# Ethernet.net
KiCad netlist of a schematic drawn in Altium Designer
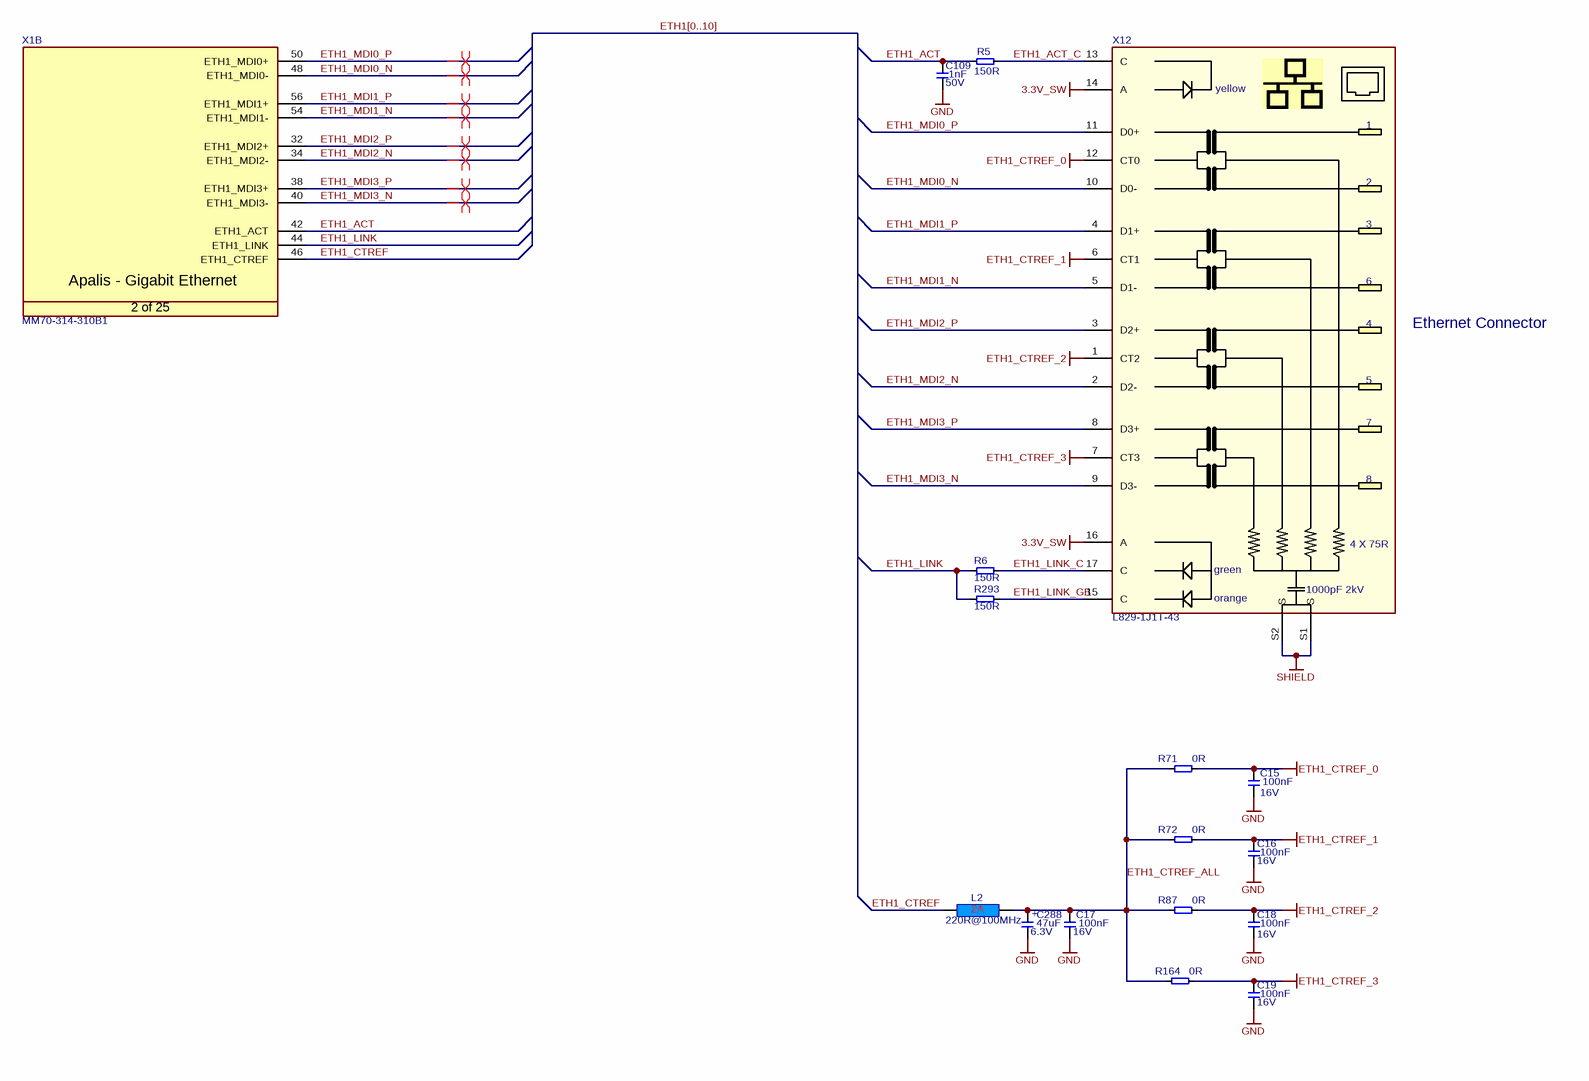
[diagram p0: Ethernet.SchDoc]

(export (version "E")
  (design (tool "Eeschema 10.0.6"))
  (components
    (comp (ref "C15")
      (value "100nF")
      (footprint "T_CAPC0603X33N")
      (description "Capacitor Ceramic X7R 100nF 16V 10% 0603")
      (fields (field (name "TOLERANCE") "10%") (field (name "RATING") "16V"))
      (libsource (lib "Apalis Evaluation Board") (part "C-X7R-100nF-16V-10%-0603"))
    )
    (comp (ref "C16")
      (value "100nF")
      (footprint "T_CAPC0603X33N")
      (description "Capacitor Ceramic X7R 100nF 16V 10% 0603")
      (fields (field (name "TOLERANCE") "10%") (field (name "RATING") "16V"))
      (libsource (lib "Apalis Evaluation Board") (part "C-X7R-100nF-16V-10%-0603"))
    )
    (comp (ref "C17")
      (value "100nF")
      (footprint "T_CAPC0603X33N")
      (description "Capacitor Ceramic X7R 100nF 16V 10% 0603")
      (fields (field (name "TOLERANCE") "10%") (field (name "RATING") "16V"))
      (libsource (lib "Apalis Evaluation Board") (part "C-X7R-100nF-16V-10%-0603"))
    )
    (comp (ref "C18")
      (value "100nF")
      (footprint "T_CAPC0603X33N")
      (description "Capacitor Ceramic X7R 100nF 16V 10% 0603")
      (fields (field (name "TOLERANCE") "10%") (field (name "RATING") "16V"))
      (libsource (lib "Apalis Evaluation Board") (part "C-X7R-100nF-16V-10%-0603"))
    )
    (comp (ref "C19")
      (value "100nF")
      (footprint "T_CAPC0603X33N")
      (description "Capacitor Ceramic X7R 100nF 16V 10% 0603")
      (fields (field (name "TOLERANCE") "10%") (field (name "RATING") "16V"))
      (libsource (lib "Apalis Evaluation Board") (part "C-X7R-100nF-16V-10%-0603"))
    )
    (comp (ref "C109")
      (value "1nF")
      (footprint "CAPC1005X60N")
      (description "Capacitor Ceramic X7R 1nF 50V 10% 0402")
      (fields (field (name "TOLERANCE") "10%") (field (name "RATING") "50V"))
      (libsource (lib "Apalis Evaluation Board") (part "C-X7R-1nF-50V-10%-0402"))
    )
    (comp (ref "C288")
      (value "47uF")
      (footprint "T_CAPMP3216X180N")
      (description "Capacitor TA 47uF 6.3V 20% 3216")
      (fields (field (name "TOLERANCE") "20%") (field (name "RATING") "6.3V"))
      (libsource (lib "Apalis Evaluation Board") (part "C-TA-47uF-6.3V-20%-3216"))
    )
    (comp (ref "L2")
      (value "220R@100MHz")
      (footprint "INDC1608X95N")
      (description "220R@100MHz 2A EMI FILTER")
      (fields (field (name "TOLERANCE") "25%"))
      (libsource (lib "Apalis Evaluation Board") (part "L-220R@100MHz-2A-25%-0603"))
    )
    (comp (ref "R5")
      (value "150R")
      (footprint "t_RESC0603X30N")
      (description "Resistor 150 ohm 63mW 1% 0603")
      (fields (field (name "TOLERANCE") "1%"))
      (libsource (lib "Apalis Evaluation Board") (part "R-150R-63mW-1%-0603"))
    )
    (comp (ref "R6")
      (value "150R")
      (footprint "t_RESC0603X30N")
      (description "Resistor 150 ohm 63mW 1% 0603")
      (fields (field (name "TOLERANCE") "1%"))
      (libsource (lib "Apalis Evaluation Board") (part "R-150R-63mW-1%-0603"))
    )
    (comp (ref "R71")
      (value "0R")
      (footprint "T_RESC0603X30N")
      (description "Resistor 0 ohm 63mW 1% 0603")
      (fields (field (name "TOLERANCE") "1%"))
      (libsource (lib "Apalis Evaluation Board") (part "R-0R-63mW-1%-0603"))
    )
    (comp (ref "R72")
      (value "0R")
      (footprint "T_RESC0603X30N")
      (description "Resistor 0 ohm 63mW 1% 0603")
      (fields (field (name "TOLERANCE") "1%"))
      (libsource (lib "Apalis Evaluation Board") (part "R-0R-63mW-1%-0603"))
    )
    (comp (ref "R87")
      (value "0R")
      (footprint "T_RESC0603X30N")
      (description "Resistor 0 ohm 63mW 1% 0603")
      (fields (field (name "TOLERANCE") "1%"))
      (libsource (lib "Apalis Evaluation Board") (part "R-0R-63mW-1%-0603"))
    )
    (comp (ref "R164")
      (value "0R")
      (footprint "T_RESC0603X30N")
      (description "Resistor 0 ohm 63mW 1% 0603")
      (fields (field (name "TOLERANCE") "1%"))
      (libsource (lib "Apalis Evaluation Board") (part "R-0R-63mW-1%-0603"))
    )
    (comp (ref "R293")
      (value "150R")
      (footprint "t_RESC0603X30N")
      (description "Resistor 150 ohm 63mW 1% 0603")
      (fields (field (name "TOLERANCE") "1%"))
      (libsource (lib "Apalis Evaluation Board") (part "R-150R-63mW-1%-0603"))
    )
    (comp (ref "X1")
      (value "CON-JAE-MM70-314-310B1-314-0.5mm")
      (footprint "T_JAE_MM70-314-310B1")
      (description "MXM3 Connector")
      (fields (field (name "MANUFACTURER PART NO.") "MM70-314-310B1"))
      (libsource (lib "Apalis Evaluation Board") (part "CON-JAE-MM70-314-310B1-314-0.5mm"))
    )
    (comp (ref "X12")
      (value "L829-1J1T-43")
      (footprint "T_BEL_L829-1J1T-43")
      (description "Low profile 10/100/1G Mag Jack")
      (fields (field (name "MANUFACTURER PART NO.") "L829-1J1T-43"))
      (libsource (lib "Apalis Evaluation Board") (part "CON-BEL-L829-1J1T-43"))
    )
  )
  (nets
    (net (code "13") (name "/ETH1_ACT") (class "Default")
      (node (ref "C109") (pin "2") (pinfunction "2_2") (pintype "passive"))
      (node (ref "R5") (pin "1") (pinfunction "1_1") (pintype "passive"))
      (node (ref "X1") (pin "42") (pinfunction "ETH1_ACT_42") (pintype "passive"))
    )
    (net (code "14") (name "/ETH1_ACT_C") (class "Default")
      (node (ref "R5") (pin "2") (pinfunction "2_2") (pintype "passive"))
      (node (ref "X12") (pin "13") (pinfunction "C_13") (pintype "passive"))
    )
    (net (code "15") (name "/ETH1_CTREF") (class "Default")
      (node (ref "L2") (pin "1") (pinfunction "1_1") (pintype "passive"))
      (node (ref "X1") (pin "46") (pinfunction "ETH1_CTREF_46") (pintype "passive"))
    )
    (net (code "16") (name "/ETH1_CTREF_ALL") (class "Default")
      (node (ref "C17") (pin "2") (pinfunction "2_2") (pintype "passive"))
      (node (ref "C288") (pin "1") (pinfunction "1_1") (pintype "passive"))
      (node (ref "L2") (pin "2") (pinfunction "2_2") (pintype "passive"))
      (node (ref "R164") (pin "1") (pinfunction "1_1") (pintype "passive"))
      (node (ref "R71") (pin "1") (pinfunction "1_1") (pintype "passive"))
      (node (ref "R72") (pin "1") (pinfunction "1_1") (pintype "passive"))
      (node (ref "R87") (pin "1") (pinfunction "1_1") (pintype "passive"))
    )
    (net (code "17") (name "/ETH1_LINK") (class "Default")
      (node (ref "R293") (pin "1") (pinfunction "1_1") (pintype "passive"))
      (node (ref "R6") (pin "1") (pinfunction "1_1") (pintype "passive"))
      (node (ref "X1") (pin "44") (pinfunction "ETH1_LINK_44") (pintype "passive"))
    )
    (net (code "18") (name "/ETH1_LINK_C") (class "Default")
      (node (ref "R6") (pin "2") (pinfunction "2_2") (pintype "passive"))
      (node (ref "X12") (pin "17") (pinfunction "C_17") (pintype "passive"))
    )
    (net (code "19") (name "/ETH1_LINK_GB") (class "Default")
      (node (ref "R293") (pin "2") (pinfunction "2_2") (pintype "passive"))
      (node (ref "X12") (pin "15") (pinfunction "C_15") (pintype "passive"))
    )
    (net (code "20") (name "/ETH1_MDI0_N") (class "Default")
      (node (ref "X1") (pin "48") (pinfunction "ETH1_MDI0-_48") (pintype "passive"))
      (node (ref "X12") (pin "10") (pinfunction "D0-_10") (pintype "passive"))
    )
    (net (code "21") (name "/ETH1_MDI0_P") (class "Default")
      (node (ref "X1") (pin "50") (pinfunction "ETH1_MDI0+_50") (pintype "passive"))
      (node (ref "X12") (pin "11") (pinfunction "D0+_11") (pintype "passive"))
    )
    (net (code "22") (name "/ETH1_MDI1_N") (class "Default")
      (node (ref "X1") (pin "54") (pinfunction "ETH1_MDI1-_54") (pintype "passive"))
      (node (ref "X12") (pin "5") (pinfunction "D1-_5") (pintype "passive"))
    )
    (net (code "23") (name "/ETH1_MDI1_P") (class "Default")
      (node (ref "X1") (pin "56") (pinfunction "ETH1_MDI1+_56") (pintype "passive"))
      (node (ref "X12") (pin "4") (pinfunction "D1+_4") (pintype "passive"))
    )
    (net (code "24") (name "/ETH1_MDI2_N") (class "Default")
      (node (ref "X1") (pin "34") (pinfunction "ETH1_MDI2-_34") (pintype "passive"))
      (node (ref "X12") (pin "2") (pinfunction "D2-_2") (pintype "passive"))
    )
    (net (code "25") (name "/ETH1_MDI2_P") (class "Default")
      (node (ref "X1") (pin "32") (pinfunction "ETH1_MDI2+_32") (pintype "passive"))
      (node (ref "X12") (pin "3") (pinfunction "D2+_3") (pintype "passive"))
    )
    (net (code "26") (name "/ETH1_MDI3_N") (class "Default")
      (node (ref "X1") (pin "40") (pinfunction "ETH1_MDI3-_40") (pintype "passive"))
      (node (ref "X12") (pin "9") (pinfunction "D3-_9") (pintype "passive"))
    )
    (net (code "27") (name "/ETH1_MDI3_P") (class "Default")
      (node (ref "X1") (pin "38") (pinfunction "ETH1_MDI3+_38") (pintype "passive"))
      (node (ref "X12") (pin "8") (pinfunction "D3+_8") (pintype "passive"))
    )
    (net (code "28") (name "3.3V_SW") (class "Default")
      (node (ref "X12") (pin "14") (pinfunction "A_14") (pintype "passive"))
      (node (ref "X12") (pin "16") (pinfunction "A_16") (pintype "passive"))
    )
    (net (code "29") (name "ETH1_CTREF_0") (class "Default")
      (node (ref "C15") (pin "2") (pinfunction "2_2") (pintype "passive"))
      (node (ref "R71") (pin "2") (pinfunction "2_2") (pintype "passive"))
      (node (ref "X12") (pin "12") (pinfunction "CT0_12") (pintype "passive"))
    )
    (net (code "30") (name "ETH1_CTREF_1") (class "Default")
      (node (ref "C16") (pin "2") (pinfunction "2_2") (pintype "passive"))
      (node (ref "R72") (pin "2") (pinfunction "2_2") (pintype "passive"))
      (node (ref "X12") (pin "6") (pinfunction "CT1_6") (pintype "passive"))
    )
    (net (code "31") (name "ETH1_CTREF_2") (class "Default")
      (node (ref "C18") (pin "2") (pinfunction "2_2") (pintype "passive"))
      (node (ref "R87") (pin "2") (pinfunction "2_2") (pintype "passive"))
      (node (ref "X12") (pin "1") (pinfunction "CT2_1") (pintype "passive"))
    )
    (net (code "32") (name "ETH1_CTREF_3") (class "Default")
      (node (ref "C19") (pin "2") (pinfunction "2_2") (pintype "passive"))
      (node (ref "R164") (pin "2") (pinfunction "2_2") (pintype "passive"))
      (node (ref "X12") (pin "7") (pinfunction "CT3_7") (pintype "passive"))
    )
    (net (code "33") (name "GND") (class "Default")
      (node (ref "C109") (pin "1") (pinfunction "1_1") (pintype "passive"))
      (node (ref "C15") (pin "1") (pinfunction "1_1") (pintype "passive"))
      (node (ref "C16") (pin "1") (pinfunction "1_1") (pintype "passive"))
      (node (ref "C17") (pin "1") (pinfunction "1_1") (pintype "passive"))
      (node (ref "C18") (pin "1") (pinfunction "1_1") (pintype "passive"))
      (node (ref "C19") (pin "1") (pinfunction "1_1") (pintype "passive"))
      (node (ref "C288") (pin "2") (pinfunction "2_2") (pintype "passive"))
    )
    (net (code "34") (name "SHIELD") (class "Default")
      (node (ref "X12") (pin "S1") (pinfunction "S_S1") (pintype "passive"))
      (node (ref "X12") (pin "S2") (pinfunction "S_S2") (pintype "passive"))
    )
  )
)
